# ws2812-cube-v1_2.net
KiCad netlist of a schematic drawn in EasyEDA
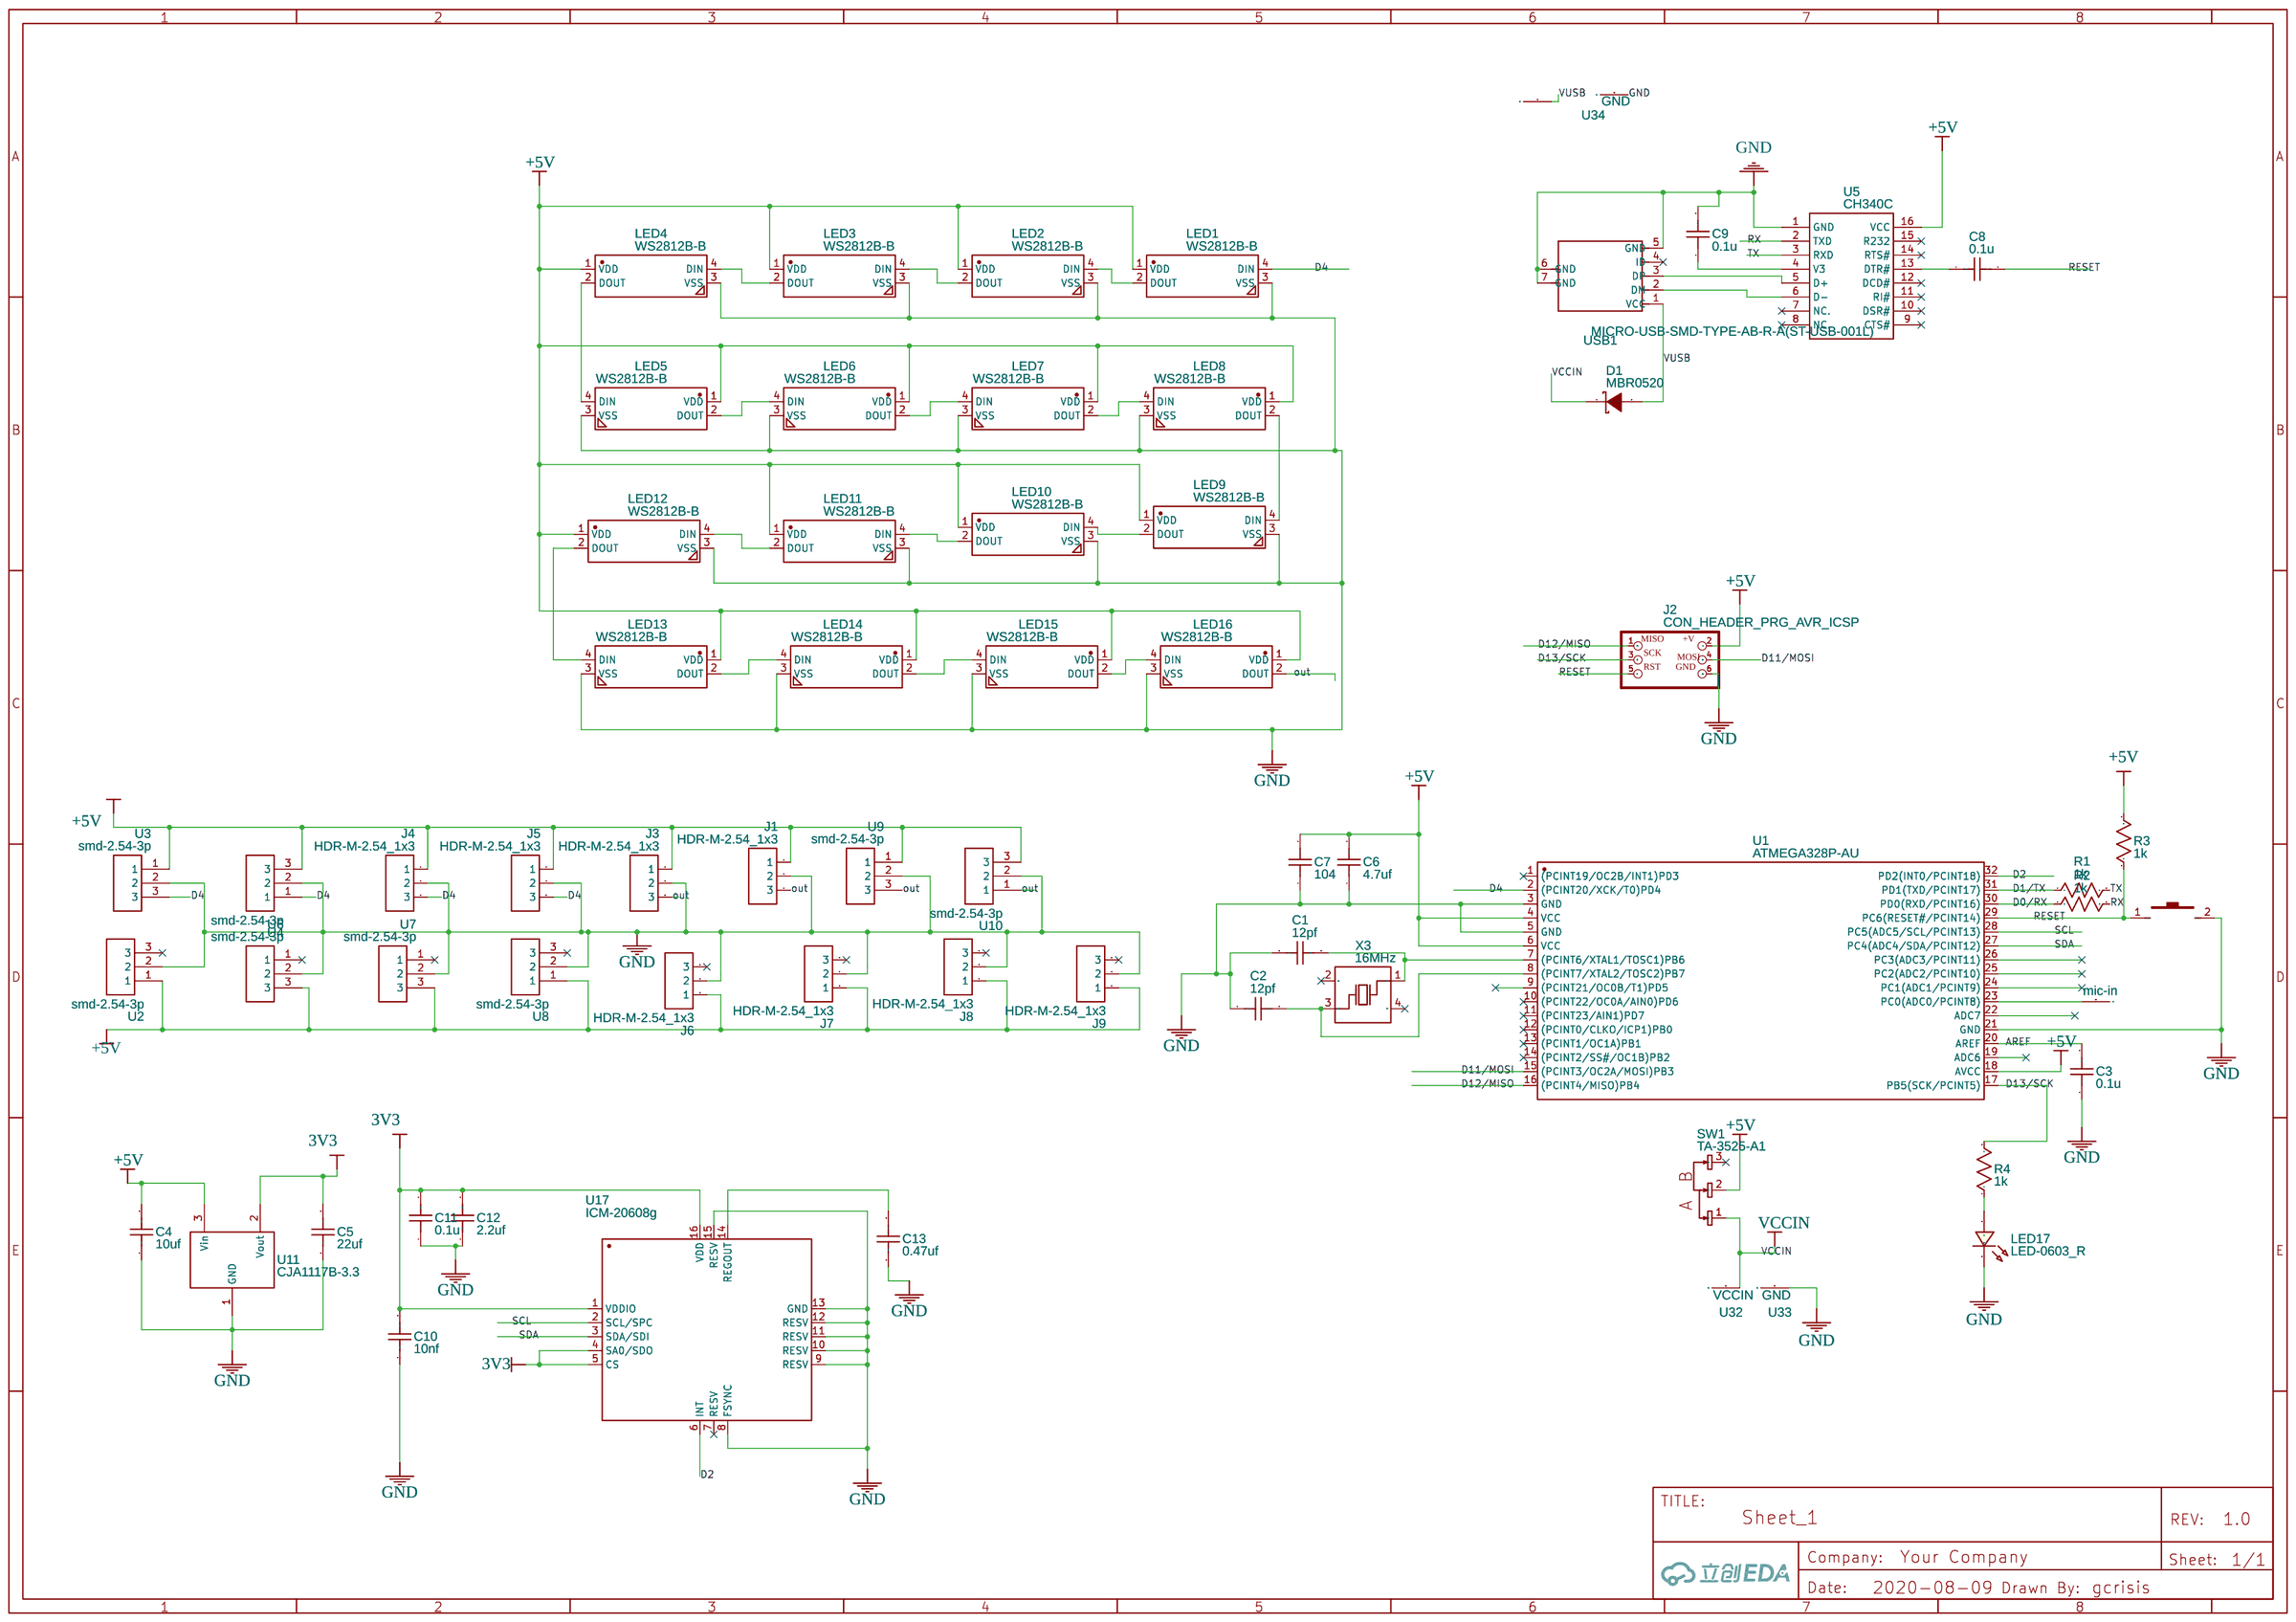
[diagram p0: schematic sheet]

(export (version "E")
  (design (tool "Eeschema 10.0.6"))
  (components
    (comp (ref "C1") (value "12pf") (libsource (lib "") (part "C_0603_US_1")))
    (comp (ref "C2") (value "12pf") (libsource (lib "") (part "C_0603_US_1")))
    (comp (ref "C3") (value "0.1u") (libsource (lib "") (part "C_0603_US")))
    (comp (ref "C4") (value "10uf") (libsource (lib "") (part "C_0603_US")))
    (comp (ref "C5") (value "22uf") (libsource (lib "") (part "C_0603_US")))
    (comp (ref "C6") (value "4.7uf") (libsource (lib "") (part "C_0603_US")))
    (comp (ref "C7") (value "104") (libsource (lib "") (part "C_0603_US")))
    (comp (ref "C8") (value "0.1u") (libsource (lib "") (part "C_0603_US_1")))
    (comp (ref "C9") (value "0.1u") (libsource (lib "") (part "C_0603_US")))
    (comp (ref "C10") (value "10nf") (libsource (lib "") (part "C_0603_US")))
    (comp (ref "C11") (value "0.1u") (libsource (lib "") (part "C_0603_US")))
    (comp (ref "C12") (value "2.2uf") (libsource (lib "") (part "C_0603_US")))
    (comp (ref "C13") (value "0.47uf") (libsource (lib "") (part "C_0603_US")))
    (comp (ref "D1")
      (value "MBR0520")
      (fields (field (name "BOM_Supplier Part") "C77335"))
      (libsource (lib "") (part "MBR0520"))
    )
    (comp (ref "J1")
      (value "HDR-M-2.54_1x3")
      (fields (field (name "BOM_Supplier Part") "C180248"))
      (libsource (lib "") (part "HDR-M-2.54_1x3_1"))
    )
    (comp (ref "J2") (value "CON_HEADER_PRG_AVR_ICSP") (libsource (lib "") (part "CON_HEADER_PRG_AVR_ICSP")))
    (comp (ref "J3")
      (value "HDR-M-2.54_1x3")
      (fields (field (name "BOM_Supplier Part") "C180248"))
      (libsource (lib "") (part "HDR-M-2.54_1x3_1"))
    )
    (comp (ref "J4")
      (value "HDR-M-2.54_1x3")
      (fields (field (name "BOM_Supplier Part") "C180248"))
      (libsource (lib "") (part "HDR-M-2.54_1x3_1"))
    )
    (comp (ref "J5")
      (value "HDR-M-2.54_1x3")
      (fields (field (name "BOM_Supplier Part") "C180248"))
      (libsource (lib "") (part "HDR-M-2.54_1x3_1"))
    )
    (comp (ref "J6")
      (value "HDR-M-2.54_1x3")
      (fields (field (name "BOM_Supplier Part") "C180248"))
      (libsource (lib "") (part "HDR-M-2.54_1x3"))
    )
    (comp (ref "J7")
      (value "HDR-M-2.54_1x3")
      (fields (field (name "BOM_Supplier Part") "C180248"))
      (libsource (lib "") (part "HDR-M-2.54_1x3"))
    )
    (comp (ref "J8")
      (value "HDR-M-2.54_1x3")
      (fields (field (name "BOM_Supplier Part") "C180248"))
      (libsource (lib "") (part "HDR-M-2.54_1x3"))
    )
    (comp (ref "J9")
      (value "HDR-M-2.54_1x3")
      (fields (field (name "BOM_Supplier Part") "C180248"))
      (libsource (lib "") (part "HDR-M-2.54_1x3"))
    )
    (comp (ref "KEY1")
      (value "3x6x2.5mm")
      (fields (field (name "BOM_Supplier Part") "C5382"))
      (libsource (lib "") (part "3x6x2.5mm"))
    )
    (comp (ref "LED1")
      (value "WS2812B-B")
      (fields (field (name "BOM_Supplier Part") "C114586"))
      (libsource (lib "") (part "WS2812B-B"))
    )
    (comp (ref "LED2")
      (value "WS2812B-B")
      (fields (field (name "BOM_Supplier Part") "C114586"))
      (libsource (lib "") (part "WS2812B-B"))
    )
    (comp (ref "LED3")
      (value "WS2812B-B")
      (fields (field (name "BOM_Supplier Part") "C114586"))
      (libsource (lib "") (part "WS2812B-B"))
    )
    (comp (ref "LED4")
      (value "WS2812B-B")
      (fields (field (name "BOM_Supplier Part") "C114586"))
      (libsource (lib "") (part "WS2812B-B"))
    )
    (comp (ref "LED5")
      (value "WS2812B-B")
      (fields (field (name "BOM_Supplier Part") "C114586"))
      (libsource (lib "") (part "WS2812B-B_1"))
    )
    (comp (ref "LED6")
      (value "WS2812B-B")
      (fields (field (name "BOM_Supplier Part") "C114586"))
      (libsource (lib "") (part "WS2812B-B_1"))
    )
    (comp (ref "LED7")
      (value "WS2812B-B")
      (fields (field (name "BOM_Supplier Part") "C114586"))
      (libsource (lib "") (part "WS2812B-B_1"))
    )
    (comp (ref "LED8")
      (value "WS2812B-B")
      (fields (field (name "BOM_Supplier Part") "C114586"))
      (libsource (lib "") (part "WS2812B-B_1"))
    )
    (comp (ref "LED9")
      (value "WS2812B-B")
      (fields (field (name "BOM_Supplier Part") "C114586"))
      (libsource (lib "") (part "WS2812B-B"))
    )
    (comp (ref "LED10")
      (value "WS2812B-B")
      (fields (field (name "BOM_Supplier Part") "C114586"))
      (libsource (lib "") (part "WS2812B-B"))
    )
    (comp (ref "LED11")
      (value "WS2812B-B")
      (fields (field (name "BOM_Supplier Part") "C114586"))
      (libsource (lib "") (part "WS2812B-B"))
    )
    (comp (ref "LED12")
      (value "WS2812B-B")
      (fields (field (name "BOM_Supplier Part") "C114586"))
      (libsource (lib "") (part "WS2812B-B"))
    )
    (comp (ref "LED13")
      (value "WS2812B-B")
      (fields (field (name "BOM_Supplier Part") "C114586"))
      (libsource (lib "") (part "WS2812B-B_1"))
    )
    (comp (ref "LED14")
      (value "WS2812B-B")
      (fields (field (name "BOM_Supplier Part") "C114586"))
      (libsource (lib "") (part "WS2812B-B_1"))
    )
    (comp (ref "LED15")
      (value "WS2812B-B")
      (fields (field (name "BOM_Supplier Part") "C114586"))
      (libsource (lib "") (part "WS2812B-B_1"))
    )
    (comp (ref "LED16")
      (value "WS2812B-B")
      (fields (field (name "BOM_Supplier Part") "C114586"))
      (libsource (lib "") (part "WS2812B-B_1"))
    )
    (comp (ref "LED17")
      (value "LED-0603_R")
      (fields
        (field (name "BOM_Manufacturer Part") "19-217/R6C-AL1M2VY/3T")
        (field (name "BOM_Supplier Part") "C72044")
      )
      (libsource (lib "") (part "LED-0603_R"))
    )
    (comp (ref "R1") (value "1k") (libsource (lib "") (part "R_0603_US_1")))
    (comp (ref "R2") (value "1k") (libsource (lib "") (part "R_0603_US_1")))
    (comp (ref "R3") (value "1k") (libsource (lib "") (part "R_0603_US")))
    (comp (ref "R4") (value "1k") (libsource (lib "") (part "R_0603_US")))
    (comp (ref "SW1")
      (value "TA-3525-A1")
      (fields (field (name "BOM_Supplier Part") "C514018"))
      (libsource (lib "") (part "TA-3525-A1"))
    )
    (comp (ref "U1")
      (value "ATMEGA328P-AU")
      (fields (field (name "BOM_Supplier Part") "C14877"))
      (libsource (lib "") (part "ATMEGA328P-AU"))
    )
    (comp (ref "U2") (value "smd-2.54-3p") (libsource (lib "") (part "smd-2.54-3p")))
    (comp (ref "U3") (value "smd-2.54-3p") (libsource (lib "") (part "smd-2.54-3p_1")))
    (comp (ref "U4") (value "smd-2.54-3p") (libsource (lib "") (part "smd-2.54-3p")))
    (comp (ref "U5")
      (value "CH340C")
      (fields (field (name "BOM_Supplier Part") "C84681"))
      (libsource (lib "") (part "CH340C"))
    )
    (comp (ref "U6") (value "smd-2.54-3p") (libsource (lib "") (part "smd-2.54-3p_1")))
    (comp (ref "U7") (value "smd-2.54-3p") (libsource (lib "") (part "smd-2.54-3p_1")))
    (comp (ref "U8") (value "smd-2.54-3p") (libsource (lib "") (part "smd-2.54-3p")))
    (comp (ref "U9") (value "smd-2.54-3p") (libsource (lib "") (part "smd-2.54-3p_1")))
    (comp (ref "U10") (value "smd-2.54-3p") (libsource (lib "") (part "smd-2.54-3p")))
    (comp (ref "U11")
      (value "CJA1117B-3.3")
      (fields (field (name "BOM_Supplier Part") "C24253"))
      (libsource (lib "") (part "CJA1117B-3.3"))
    )
    (comp (ref "U12") (value "mic-in") (libsource (lib "") (part "PAD_1")))
    (comp (ref "U17")
      (value "ICM-20608g")
      (fields (field (name "BOM_Manufacturer Part") "ICM-20602") (field (name "BOM_Supplier Part") "C97633"))
      (libsource (lib "") (part "ICM-20602"))
    )
    (comp (ref "U32") (value "VCCIN") (libsource (lib "") (part "PAD")))
    (comp (ref "U33") (value "GND") (libsource (lib "") (part "PAD")))
    (comp (ref "U34") (value "GND") (libsource (lib "") (part "PAD")))
    (comp (ref "U35") (value "VUSB") (libsource (lib "") (part "PAD")))
    (comp (ref "USB1")
      (value "MICRO-USB-SMD-TYPE-AB-R-A(ST-USB-001L)")
      (fields (field (name "BOM_Manufacturer Part") "?"))
      (libsource (lib "") (part "MICRO-USB-SMD-TYPE-AB-R-A(ST-USB-001L)"))
    )
    (comp (ref "X3")
      (value "16MHz")
      (fields
        (field (name "BOM_Manufacturer Part") "X1E0000210375000G")
        (field (name "BOM_Supplier Part") "C89379")
      )
      (libsource (lib "") (part "X1E0000210375000G"))
    )
  )
  (nets
    (net (code "1") (name "+5V") (class "Default")
      (node (ref "C4") (pin "2") (pinfunction "2_2") (pintype "unspecified"))
      (node (ref "C6") (pin "2") (pinfunction "2_2") (pintype "unspecified"))
      (node (ref "C7") (pin "2") (pinfunction "2_2") (pintype "unspecified"))
      (node (ref "J1") (pin "1") (pinfunction "1_1") (pintype "input"))
      (node (ref "J2") (pin "2") (pinfunction "+V_2") (pintype "unspecified"))
      (node (ref "J3") (pin "1") (pinfunction "1_1") (pintype "input"))
      (node (ref "J4") (pin "1") (pinfunction "1_1") (pintype "input"))
      (node (ref "J5") (pin "1") (pinfunction "1_1") (pintype "input"))
      (node (ref "J6") (pin "1") (pinfunction "1_1") (pintype "input"))
      (node (ref "J7") (pin "1") (pinfunction "1_1") (pintype "input"))
      (node (ref "J8") (pin "1") (pinfunction "1_1") (pintype "input"))
      (node (ref "J9") (pin "1") (pinfunction "1_1") (pintype "input"))
      (node (ref "LED1") (pin "1") (pinfunction "VDD_1") (pintype "unspecified"))
      (node (ref "LED10") (pin "1") (pinfunction "VDD_1") (pintype "unspecified"))
      (node (ref "LED11") (pin "1") (pinfunction "VDD_1") (pintype "unspecified"))
      (node (ref "LED12") (pin "1") (pinfunction "VDD_1") (pintype "unspecified"))
      (node (ref "LED13") (pin "1") (pinfunction "VDD_1") (pintype "unspecified"))
      (node (ref "LED14") (pin "1") (pinfunction "VDD_1") (pintype "unspecified"))
      (node (ref "LED15") (pin "1") (pinfunction "VDD_1") (pintype "unspecified"))
      (node (ref "LED16") (pin "1") (pinfunction "VDD_1") (pintype "unspecified"))
      (node (ref "LED2") (pin "1") (pinfunction "VDD_1") (pintype "unspecified"))
      (node (ref "LED3") (pin "1") (pinfunction "VDD_1") (pintype "unspecified"))
      (node (ref "LED4") (pin "1") (pinfunction "VDD_1") (pintype "unspecified"))
      (node (ref "LED5") (pin "1") (pinfunction "VDD_1") (pintype "unspecified"))
      (node (ref "LED6") (pin "1") (pinfunction "VDD_1") (pintype "unspecified"))
      (node (ref "LED7") (pin "1") (pinfunction "VDD_1") (pintype "unspecified"))
      (node (ref "LED8") (pin "1") (pinfunction "VDD_1") (pintype "unspecified"))
      (node (ref "LED9") (pin "1") (pinfunction "VDD_1") (pintype "unspecified"))
      (node (ref "R3") (pin "2") (pinfunction "2_2") (pintype "unspecified"))
      (node (ref "SW1") (pin "2") (pinfunction "2_2") (pintype "unspecified"))
      (node (ref "U1") (pin "18") (pinfunction "AVCC_18") (pintype "unspecified"))
      (node (ref "U1") (pin "4") (pinfunction "VCC_4") (pintype "unspecified"))
      (node (ref "U1") (pin "6") (pinfunction "VCC_6") (pintype "unspecified"))
      (node (ref "U10") (pin "3") (pinfunction "3_3") (pintype "unspecified"))
      (node (ref "U11") (pin "3") (pinfunction "Vin_3") (pintype "unspecified"))
      (node (ref "U2") (pin "1") (pinfunction "1_1") (pintype "unspecified"))
      (node (ref "U3") (pin "1") (pinfunction "1_1") (pintype "unspecified"))
      (node (ref "U4") (pin "3") (pinfunction "3_3") (pintype "unspecified"))
      (node (ref "U5") (pin "16") (pinfunction "VCC_16") (pintype "unspecified"))
      (node (ref "U6") (pin "3") (pinfunction "3_3") (pintype "unspecified"))
      (node (ref "U7") (pin "3") (pinfunction "3_3") (pintype "unspecified"))
      (node (ref "U8") (pin "1") (pinfunction "1_1") (pintype "unspecified"))
      (node (ref "U9") (pin "1") (pinfunction "1_1") (pintype "unspecified"))
    )
    (net (code "2") (name "/AREF") (class "Default")
      (node (ref "C3") (pin "2") (pinfunction "2_2") (pintype "unspecified"))
      (node (ref "U1") (pin "20") (pinfunction "AREF_20") (pintype "unspecified"))
    )
    (net (code "3") (name "/D0{slash}RX") (class "Default")
      (node (ref "R2") (pin "1") (pinfunction "1_1") (pintype "unspecified"))
      (node (ref "U1") (pin "30") (pinfunction "PD0(RXD/PCINT16)_30") (pintype "unspecified"))
    )
    (net (code "4") (name "/D1{slash}TX") (class "Default")
      (node (ref "R1") (pin "1") (pinfunction "1_1") (pintype "unspecified"))
      (node (ref "U1") (pin "31") (pinfunction "PD1(TXD/PCINT17)_31") (pintype "unspecified"))
    )
    (net (code "5") (name "/D2") (class "Default")
      (node (ref "U1") (pin "32") (pinfunction "PD2(INT0/PCINT18)_32") (pintype "unspecified"))
      (node (ref "U17") (pin "6") (pinfunction "INT_6") (pintype "unspecified"))
    )
    (net (code "6") (name "/D4") (class "Default")
      (node (ref "J4") (pin "3") (pinfunction "3_3") (pintype "input"))
      (node (ref "J5") (pin "3") (pinfunction "3_3") (pintype "input"))
      (node (ref "LED1") (pin "4") (pinfunction "DIN_4") (pintype "unspecified"))
      (node (ref "U1") (pin "2") (pinfunction "(PCINT20/XCK/T0)PD4_2") (pintype "unspecified"))
      (node (ref "U3") (pin "3") (pinfunction "3_3") (pintype "unspecified"))
      (node (ref "U4") (pin "1") (pinfunction "1_1") (pintype "unspecified"))
    )
    (net (code "7") (name "/D11{slash}MOSI") (class "Default")
      (node (ref "J2") (pin "4") (pinfunction "MOSI_4") (pintype "unspecified"))
      (node (ref "U1") (pin "15") (pinfunction "(PCINT3/OC2A/MOSI)PB3_15") (pintype "unspecified"))
    )
    (net (code "8") (name "/D12{slash}MISO") (class "Default")
      (node (ref "J2") (pin "1") (pinfunction "MISO_1") (pintype "unspecified"))
      (node (ref "U1") (pin "16") (pinfunction "(PCINT4/MISO)PB4_16") (pintype "unspecified"))
    )
    (net (code "9") (name "/D13{slash}SCK") (class "Default")
      (node (ref "J2") (pin "3") (pinfunction "SCK_3") (pintype "unspecified"))
      (node (ref "R4") (pin "2") (pinfunction "2_2") (pintype "unspecified"))
      (node (ref "U1") (pin "17") (pinfunction "PB5(SCK/PCINT5)_17") (pintype "unspecified"))
    )
    (net (code "10") (name "/RESET") (class "Default")
      (node (ref "C8") (pin "2") (pinfunction "2_2") (pintype "unspecified"))
      (node (ref "J2") (pin "5") (pinfunction "RST_5") (pintype "unspecified"))
      (node (ref "KEY1") (pin "1") (pinfunction "1_1") (pintype "input"))
      (node (ref "R3") (pin "1") (pinfunction "1_1") (pintype "unspecified"))
      (node (ref "U1") (pin "29") (pinfunction "PC6(RESET#/PCINT14)_29") (pintype "unspecified"))
    )
    (net (code "11") (name "/RX") (class "Default")
      (node (ref "R2") (pin "2") (pinfunction "2_2") (pintype "unspecified"))
      (node (ref "U5") (pin "2") (pinfunction "TXD_2") (pintype "unspecified"))
    )
    (net (code "12") (name "/SCL") (class "Default")
      (node (ref "U1") (pin "28") (pinfunction "PC5(ADC5/SCL/PCINT13)_28") (pintype "unspecified"))
      (node (ref "U17") (pin "2") (pinfunction "SCL/SPC_2") (pintype "unspecified"))
    )
    (net (code "13") (name "/SDA") (class "Default")
      (node (ref "U1") (pin "27") (pinfunction "PC4(ADC4/SDA/PCINT12)_27") (pintype "unspecified"))
      (node (ref "U17") (pin "3") (pinfunction "SDA/SDI_3") (pintype "unspecified"))
    )
    (net (code "14") (name "/TX") (class "Default")
      (node (ref "R1") (pin "2") (pinfunction "2_2") (pintype "unspecified"))
      (node (ref "U5") (pin "3") (pinfunction "RXD_3") (pintype "unspecified"))
    )
    (net (code "15") (name "/VUSB") (class "Default")
      (node (ref "D1") (pin "2") (pinfunction "A_2") (pintype "unspecified"))
      (node (ref "U35") (pin "P$1") (pinfunction "P$1_P$1") (pintype "unspecified"))
      (node (ref "USB1") (pin "1") (pinfunction "VCC_1") (pintype "unspecified"))
    )
    (net (code "16") (name "/out") (class "Default")
      (node (ref "J1") (pin "3") (pinfunction "3_3") (pintype "input"))
      (node (ref "J3") (pin "3") (pinfunction "3_3") (pintype "input"))
      (node (ref "LED16") (pin "2") (pinfunction "DOUT_2") (pintype "unspecified"))
      (node (ref "U10") (pin "1") (pinfunction "1_1") (pintype "unspecified"))
      (node (ref "U9") (pin "3") (pinfunction "3_3") (pintype "unspecified"))
    )
    (net (code "17") (name "3V3") (class "Default")
      (node (ref "C10") (pin "2") (pinfunction "2_2") (pintype "unspecified"))
      (node (ref "C11") (pin "2") (pinfunction "2_2") (pintype "unspecified"))
      (node (ref "C12") (pin "2") (pinfunction "2_2") (pintype "unspecified"))
      (node (ref "C5") (pin "2") (pinfunction "2_2") (pintype "unspecified"))
      (node (ref "U11") (pin "2") (pinfunction "Vout_2") (pintype "unspecified"))
      (node (ref "U17") (pin "1") (pinfunction "VDDIO_1") (pintype "unspecified"))
      (node (ref "U17") (pin "16") (pinfunction "VDD_16") (pintype "unspecified"))
      (node (ref "U17") (pin "4") (pinfunction "SA0/SDO_4") (pintype "unspecified"))
      (node (ref "U17") (pin "5") (pinfunction "CS_5") (pintype "unspecified"))
    )
    (net (code "18") (name "GND") (class "Default")
      (node (ref "C1") (pin "1") (pinfunction "1_1") (pintype "unspecified"))
      (node (ref "C10") (pin "1") (pinfunction "1_1") (pintype "unspecified"))
      (node (ref "C11") (pin "1") (pinfunction "1_1") (pintype "unspecified"))
      (node (ref "C12") (pin "1") (pinfunction "1_1") (pintype "unspecified"))
      (node (ref "C13") (pin "1") (pinfunction "1_1") (pintype "unspecified"))
      (node (ref "C2") (pin "1") (pinfunction "1_1") (pintype "unspecified"))
      (node (ref "C3") (pin "1") (pinfunction "1_1") (pintype "unspecified"))
      (node (ref "C4") (pin "1") (pinfunction "1_1") (pintype "unspecified"))
      (node (ref "C5") (pin "1") (pinfunction "1_1") (pintype "unspecified"))
      (node (ref "C6") (pin "1") (pinfunction "1_1") (pintype "unspecified"))
      (node (ref "C7") (pin "1") (pinfunction "1_1") (pintype "unspecified"))
      (node (ref "C9") (pin "2") (pinfunction "2_2") (pintype "unspecified"))
      (node (ref "J1") (pin "2") (pinfunction "2_2") (pintype "input"))
      (node (ref "J2") (pin "6") (pinfunction "GND_6") (pintype "unspecified"))
      (node (ref "J3") (pin "2") (pinfunction "2_2") (pintype "input"))
      (node (ref "J4") (pin "2") (pinfunction "2_2") (pintype "input"))
      (node (ref "J5") (pin "2") (pinfunction "2_2") (pintype "input"))
      (node (ref "J6") (pin "2") (pinfunction "2_2") (pintype "input"))
      (node (ref "J7") (pin "2") (pinfunction "2_2") (pintype "input"))
      (node (ref "J8") (pin "2") (pinfunction "2_2") (pintype "input"))
      (node (ref "J9") (pin "2") (pinfunction "2_2") (pintype "input"))
      (node (ref "KEY1") (pin "2") (pinfunction "2_2") (pintype "input"))
      (node (ref "LED1") (pin "3") (pinfunction "VSS_3") (pintype "unspecified"))
      (node (ref "LED10") (pin "3") (pinfunction "VSS_3") (pintype "unspecified"))
      (node (ref "LED11") (pin "3") (pinfunction "VSS_3") (pintype "unspecified"))
      (node (ref "LED12") (pin "3") (pinfunction "VSS_3") (pintype "unspecified"))
      (node (ref "LED13") (pin "3") (pinfunction "VSS_3") (pintype "unspecified"))
      (node (ref "LED14") (pin "3") (pinfunction "VSS_3") (pintype "unspecified"))
      (node (ref "LED15") (pin "3") (pinfunction "VSS_3") (pintype "unspecified"))
      (node (ref "LED16") (pin "3") (pinfunction "VSS_3") (pintype "unspecified"))
      (node (ref "LED17") (pin "2") (pinfunction "2_2") (pintype "unspecified"))
      (node (ref "LED2") (pin "3") (pinfunction "VSS_3") (pintype "unspecified"))
      (node (ref "LED3") (pin "3") (pinfunction "VSS_3") (pintype "unspecified"))
      (node (ref "LED4") (pin "3") (pinfunction "VSS_3") (pintype "unspecified"))
      (node (ref "LED5") (pin "3") (pinfunction "VSS_3") (pintype "unspecified"))
      (node (ref "LED6") (pin "3") (pinfunction "VSS_3") (pintype "unspecified"))
      (node (ref "LED7") (pin "3") (pinfunction "VSS_3") (pintype "unspecified"))
      (node (ref "LED8") (pin "3") (pinfunction "VSS_3") (pintype "unspecified"))
      (node (ref "LED9") (pin "3") (pinfunction "VSS_3") (pintype "unspecified"))
      (node (ref "U1") (pin "21") (pinfunction "GND_21") (pintype "unspecified"))
      (node (ref "U1") (pin "3") (pinfunction "GND_3") (pintype "unspecified"))
      (node (ref "U1") (pin "5") (pinfunction "GND_5") (pintype "unspecified"))
      (node (ref "U10") (pin "2") (pinfunction "2_2") (pintype "unspecified"))
      (node (ref "U11") (pin "1") (pinfunction "GND_1") (pintype "unspecified"))
      (node (ref "U17") (pin "10") (pinfunction "RESV_10") (pintype "unspecified"))
      (node (ref "U17") (pin "11") (pinfunction "RESV_11") (pintype "unspecified"))
      (node (ref "U17") (pin "12") (pinfunction "RESV_12") (pintype "unspecified"))
      (node (ref "U17") (pin "13") (pinfunction "GND_13") (pintype "unspecified"))
      (node (ref "U17") (pin "15") (pinfunction "RESV_15") (pintype "unspecified"))
      (node (ref "U17") (pin "8") (pinfunction "FSYNC_8") (pintype "unspecified"))
      (node (ref "U17") (pin "9") (pinfunction "RESV_9") (pintype "unspecified"))
      (node (ref "U2") (pin "2") (pinfunction "2_2") (pintype "unspecified"))
      (node (ref "U3") (pin "2") (pinfunction "2_2") (pintype "unspecified"))
      (node (ref "U33") (pin "P$1") (pinfunction "P$1_P$1") (pintype "unspecified"))
      (node (ref "U34") (pin "P$1") (pinfunction "P$1_P$1") (pintype "unspecified"))
      (node (ref "U4") (pin "2") (pinfunction "2_2") (pintype "unspecified"))
      (node (ref "U5") (pin "1") (pinfunction "GND_1") (pintype "unspecified"))
      (node (ref "U6") (pin "2") (pinfunction "2_2") (pintype "unspecified"))
      (node (ref "U7") (pin "2") (pinfunction "2_2") (pintype "unspecified"))
      (node (ref "U8") (pin "2") (pinfunction "2_2") (pintype "unspecified"))
      (node (ref "U9") (pin "2") (pinfunction "2_2") (pintype "unspecified"))
      (node (ref "USB1") (pin "5") (pinfunction "GND_5") (pintype "unspecified"))
      (node (ref "USB1") (pin "6") (pinfunction "GND_6") (pintype "unspecified"))
      (node (ref "USB1") (pin "7") (pinfunction "GND_7") (pintype "unspecified"))
    )
    (net (code "19") (name "Net-(LED1-DOUT)") (class "Default")
      (node (ref "LED1") (pin "2") (pinfunction "DOUT_2") (pintype "unspecified"))
      (node (ref "LED2") (pin "4") (pinfunction "DIN_4") (pintype "unspecified"))
    )
    (net (code "20") (name "Net-(LED2-DOUT)") (class "Default")
      (node (ref "LED2") (pin "2") (pinfunction "DOUT_2") (pintype "unspecified"))
      (node (ref "LED3") (pin "4") (pinfunction "DIN_4") (pintype "unspecified"))
    )
    (net (code "21") (name "Net-(LED3-DOUT)") (class "Default")
      (node (ref "LED3") (pin "2") (pinfunction "DOUT_2") (pintype "unspecified"))
      (node (ref "LED4") (pin "4") (pinfunction "DIN_4") (pintype "unspecified"))
    )
    (net (code "22") (name "Net-(LED4-DOUT)") (class "Default")
      (node (ref "LED4") (pin "2") (pinfunction "DOUT_2") (pintype "unspecified"))
      (node (ref "LED5") (pin "4") (pinfunction "DIN_4") (pintype "unspecified"))
    )
    (net (code "23") (name "Net-(LED5-DOUT)") (class "Default")
      (node (ref "LED5") (pin "2") (pinfunction "DOUT_2") (pintype "unspecified"))
      (node (ref "LED6") (pin "4") (pinfunction "DIN_4") (pintype "unspecified"))
    )
    (net (code "24") (name "Net-(LED6-DOUT)") (class "Default")
      (node (ref "LED6") (pin "2") (pinfunction "DOUT_2") (pintype "unspecified"))
      (node (ref "LED7") (pin "4") (pinfunction "DIN_4") (pintype "unspecified"))
    )
    (net (code "25") (name "Net-(LED7-DOUT)") (class "Default")
      (node (ref "LED7") (pin "2") (pinfunction "DOUT_2") (pintype "unspecified"))
      (node (ref "LED8") (pin "4") (pinfunction "DIN_4") (pintype "unspecified"))
    )
    (net (code "26") (name "Net-(LED8-DOUT)") (class "Default")
      (node (ref "LED8") (pin "2") (pinfunction "DOUT_2") (pintype "unspecified"))
      (node (ref "LED9") (pin "4") (pinfunction "DIN_4") (pintype "unspecified"))
    )
    (net (code "27") (name "Net-(LED10-DIN)") (class "Default")
      (node (ref "LED10") (pin "4") (pinfunction "DIN_4") (pintype "unspecified"))
      (node (ref "LED9") (pin "2") (pinfunction "DOUT_2") (pintype "unspecified"))
    )
    (net (code "28") (name "Net-(LED10-DOUT)") (class "Default")
      (node (ref "LED10") (pin "2") (pinfunction "DOUT_2") (pintype "unspecified"))
      (node (ref "LED11") (pin "4") (pinfunction "DIN_4") (pintype "unspecified"))
    )
    (net (code "29") (name "Net-(LED11-DOUT)") (class "Default")
      (node (ref "LED11") (pin "2") (pinfunction "DOUT_2") (pintype "unspecified"))
      (node (ref "LED12") (pin "4") (pinfunction "DIN_4") (pintype "unspecified"))
    )
    (net (code "30") (name "Net-(LED12-DOUT)") (class "Default")
      (node (ref "LED12") (pin "2") (pinfunction "DOUT_2") (pintype "unspecified"))
      (node (ref "LED13") (pin "4") (pinfunction "DIN_4") (pintype "unspecified"))
    )
    (net (code "31") (name "Net-(LED13-DOUT)") (class "Default")
      (node (ref "LED13") (pin "2") (pinfunction "DOUT_2") (pintype "unspecified"))
      (node (ref "LED14") (pin "4") (pinfunction "DIN_4") (pintype "unspecified"))
    )
    (net (code "32") (name "Net-(LED14-DOUT)") (class "Default")
      (node (ref "LED14") (pin "2") (pinfunction "DOUT_2") (pintype "unspecified"))
      (node (ref "LED15") (pin "4") (pinfunction "DIN_4") (pintype "unspecified"))
    )
    (net (code "33") (name "Net-(LED15-DOUT)") (class "Default")
      (node (ref "LED15") (pin "2") (pinfunction "DOUT_2") (pintype "unspecified"))
      (node (ref "LED16") (pin "4") (pinfunction "DIN_4") (pintype "unspecified"))
    )
    (net (code "34") (name "Net-(LED17-Pad1)") (class "Default")
      (node (ref "LED17") (pin "1") (pinfunction "1_1") (pintype "unspecified"))
      (node (ref "R4") (pin "1") (pinfunction "1_1") (pintype "unspecified"))
    )
    (net (code "35") (name "Net-(U1-(PCINT6{slash}XTAL1{slash}TOSC1)PB6)") (class "Default")
      (node (ref "C1") (pin "2") (pinfunction "2_2") (pintype "unspecified"))
      (node (ref "U1") (pin "7") (pinfunction "(PCINT6/XTAL1/TOSC1)PB6_7") (pintype "unspecified"))
      (node (ref "X3") (pin "1") (pinfunction "OSC1_1") (pintype "unspecified"))
    )
    (net (code "36") (name "Net-(U1-(PCINT7{slash}XTAL2{slash}TOSC2)PB7)") (class "Default")
      (node (ref "C2") (pin "2") (pinfunction "2_2") (pintype "unspecified"))
      (node (ref "U1") (pin "8") (pinfunction "(PCINT7/XTAL2/TOSC2)PB7_8") (pintype "unspecified"))
      (node (ref "X3") (pin "3") (pinfunction "OSC2_3") (pintype "unspecified"))
    )
    (net (code "37") (name "Net-(U1-PC0(ADC0{slash}PCINT8))") (class "Default")
      (node (ref "U1") (pin "23") (pinfunction "PC0(ADC0/PCINT8)_23") (pintype "unspecified"))
      (node (ref "U12") (pin "P$1") (pinfunction "P$1_P$1") (pintype "unspecified"))
    )
    (net (code "38") (name "Net-(U5-D+)") (class "Default")
      (node (ref "U5") (pin "5") (pinfunction "D+_5") (pintype "unspecified"))
      (node (ref "USB1") (pin "3") (pinfunction "DP_3") (pintype "unspecified"))
    )
    (net (code "39") (name "Net-(U5-D-)") (class "Default")
      (node (ref "U5") (pin "6") (pinfunction "D-_6") (pintype "unspecified"))
      (node (ref "USB1") (pin "2") (pinfunction "DM_2") (pintype "unspecified"))
    )
    (net (code "40") (name "Net-(U5-DTR#)") (class "Default")
      (node (ref "C8") (pin "1") (pinfunction "1_1") (pintype "unspecified"))
      (node (ref "U5") (pin "13") (pinfunction "DTR#_13") (pintype "unspecified"))
    )
    (net (code "41") (name "Net-(U5-V3)") (class "Default")
      (node (ref "C9") (pin "1") (pinfunction "1_1") (pintype "unspecified"))
      (node (ref "U5") (pin "4") (pinfunction "V3_4") (pintype "unspecified"))
    )
    (net (code "42") (name "Net-(U17-REGOUT)") (class "Default")
      (node (ref "C13") (pin "2") (pinfunction "2_2") (pintype "unspecified"))
      (node (ref "U17") (pin "14") (pinfunction "REGOUT_14") (pintype "unspecified"))
    )
    (net (code "43") (name "VCCIN") (class "Default")
      (node (ref "D1") (pin "1") (pinfunction "K_1") (pintype "unspecified"))
      (node (ref "SW1") (pin "1") (pinfunction "1_1") (pintype "unspecified"))
      (node (ref "U32") (pin "P$1") (pinfunction "P$1_P$1") (pintype "unspecified"))
    )
    (net (code "44") (name "unconnected-(J6-Pad3)") (class "Default")
      (node (ref "J6") (pin "3") (pinfunction "3_3") (pintype "input+no_connect"))
    )
    (net (code "45") (name "unconnected-(J7-Pad3)") (class "Default")
      (node (ref "J7") (pin "3") (pinfunction "3_3") (pintype "input+no_connect"))
    )
    (net (code "46") (name "unconnected-(J8-Pad3)") (class "Default")
      (node (ref "J8") (pin "3") (pinfunction "3_3") (pintype "input+no_connect"))
    )
    (net (code "47") (name "unconnected-(J9-Pad3)") (class "Default")
      (node (ref "J9") (pin "3") (pinfunction "3_3") (pintype "input+no_connect"))
    )
    (net (code "48") (name "unconnected-(SW1-Pad3)") (class "Default")
      (node (ref "SW1") (pin "3") (pinfunction "3_3") (pintype "unspecified+no_connect"))
    )
    (net (code "49") (name "unconnected-(U1-(PCINT0{slash}CLKO{slash}ICP1)PB0-Pad12)") (class "Default")
      (node (ref "U1") (pin "12") (pinfunction "(PCINT0/CLKO/ICP1)PB0_12") (pintype "unspecified+no_connect"))
    )
    (net (code "50") (name "unconnected-(U1-(PCINT1{slash}OC1A)PB1-Pad13)") (class "Default")
      (node (ref "U1") (pin "13") (pinfunction "(PCINT1/OC1A)PB1_13") (pintype "unspecified+no_connect"))
    )
    (net (code "51") (name "unconnected-(U1-(PCINT2{slash}SS#{slash}OC1B)PB2-Pad14)") (class "Default")
      (node (ref "U1") (pin "14") (pinfunction "(PCINT2/SS#/OC1B)PB2_14") (pintype "unspecified+no_connect"))
    )
    (net (code "52") (name "unconnected-(U1-(PCINT19{slash}OC2B{slash}INT1)PD3-Pad1)") (class "Default")
      (node (ref "U1") (pin "1") (pinfunction "(PCINT19/OC2B/INT1)PD3_1") (pintype "unspecified+no_connect"))
    )
    (net (code "53") (name "unconnected-(U1-(PCINT21{slash}OC0B{slash}T1)PD5-Pad9)") (class "Default")
      (node (ref "U1") (pin "9") (pinfunction "(PCINT21/OC0B/T1)PD5_9") (pintype "unspecified+no_connect"))
    )
    (net (code "54") (name "unconnected-(U1-(PCINT22{slash}OC0A{slash}AIN0)PD6-Pad10)") (class "Default")
      (node (ref "U1") (pin "10") (pinfunction "(PCINT22/OC0A/AIN0)PD6_10") (pintype "unspecified+no_connect"))
    )
    (net (code "55") (name "unconnected-(U1-(PCINT23{slash}AIN1)PD7-Pad11)") (class "Default")
      (node (ref "U1") (pin "11") (pinfunction "(PCINT23/AIN1)PD7_11") (pintype "unspecified+no_connect"))
    )
    (net (code "56") (name "unconnected-(U1-ADC6-Pad19)") (class "Default")
      (node (ref "U1") (pin "19") (pinfunction "ADC6_19") (pintype "unspecified+no_connect"))
    )
    (net (code "57") (name "unconnected-(U1-ADC7-Pad22)") (class "Default")
      (node (ref "U1") (pin "22") (pinfunction "ADC7_22") (pintype "unspecified+no_connect"))
    )
    (net (code "58") (name "unconnected-(U1-PC1(ADC1{slash}PCINT9)-Pad24)") (class "Default")
      (node (ref "U1") (pin "24") (pinfunction "PC1(ADC1/PCINT9)_24") (pintype "unspecified+no_connect"))
    )
    (net (code "59") (name "unconnected-(U1-PC2(ADC2{slash}PCINT10)-Pad25)") (class "Default")
      (node (ref "U1") (pin "25") (pinfunction "PC2(ADC2/PCINT10)_25") (pintype "unspecified+no_connect"))
    )
    (net (code "60") (name "unconnected-(U1-PC3(ADC3{slash}PCINT11)-Pad26)") (class "Default")
      (node (ref "U1") (pin "26") (pinfunction "PC3(ADC3/PCINT11)_26") (pintype "unspecified+no_connect"))
    )
    (net (code "61") (name "unconnected-(U2-Pad3)") (class "Default")
      (node (ref "U2") (pin "3") (pinfunction "3_3") (pintype "unspecified+no_connect"))
    )
    (net (code "62") (name "unconnected-(U5-CTS#-Pad9)") (class "Default")
      (node (ref "U5") (pin "9") (pinfunction "CTS#_9") (pintype "unspecified+no_connect"))
    )
    (net (code "63") (name "unconnected-(U5-DCD#-Pad12)") (class "Default")
      (node (ref "U5") (pin "12") (pinfunction "DCD#_12") (pintype "unspecified+no_connect"))
    )
    (net (code "64") (name "unconnected-(U5-DSR#-Pad10)") (class "Default")
      (node (ref "U5") (pin "10") (pinfunction "DSR#_10") (pintype "unspecified+no_connect"))
    )
    (net (code "65") (name "unconnected-(U5-NC.-Pad7)") (class "Default")
      (node (ref "U5") (pin "7") (pinfunction "NC._7") (pintype "unspecified+no_connect"))
    )
    (net (code "66") (name "unconnected-(U5-NC.-Pad8)") (class "Default")
      (node (ref "U5") (pin "8") (pinfunction "NC._8") (pintype "unspecified+no_connect"))
    )
    (net (code "67") (name "unconnected-(U5-R232-Pad15)") (class "Default")
      (node (ref "U5") (pin "15") (pinfunction "R232_15") (pintype "unspecified+no_connect"))
    )
    (net (code "68") (name "unconnected-(U5-RI#-Pad11)") (class "Default")
      (node (ref "U5") (pin "11") (pinfunction "RI#_11") (pintype "unspecified+no_connect"))
    )
    (net (code "69") (name "unconnected-(U5-RTS#-Pad14)") (class "Default")
      (node (ref "U5") (pin "14") (pinfunction "RTS#_14") (pintype "unspecified+no_connect"))
    )
    (net (code "70") (name "unconnected-(U6-Pad1)") (class "Default")
      (node (ref "U6") (pin "1") (pinfunction "1_1") (pintype "unspecified+no_connect"))
    )
    (net (code "71") (name "unconnected-(U7-Pad1)") (class "Default")
      (node (ref "U7") (pin "1") (pinfunction "1_1") (pintype "unspecified+no_connect"))
    )
    (net (code "72") (name "unconnected-(U8-Pad3)") (class "Default")
      (node (ref "U8") (pin "3") (pinfunction "3_3") (pintype "unspecified+no_connect"))
    )
    (net (code "73") (name "unconnected-(U17-RESV-Pad7)") (class "Default")
      (node (ref "U17") (pin "7") (pinfunction "RESV_7") (pintype "unspecified+no_connect"))
    )
    (net (code "74") (name "unconnected-(USB1-ID-Pad4)") (class "Default")
      (node (ref "USB1") (pin "4") (pinfunction "ID_4") (pintype "unspecified+no_connect"))
    )
    (net (code "75") (name "unconnected-(X3-GND-Pad2)") (class "Default")
      (node (ref "X3") (pin "2") (pinfunction "GND_2") (pintype "unspecified+no_connect"))
    )
    (net (code "76") (name "unconnected-(X3-GND-Pad4)") (class "Default")
      (node (ref "X3") (pin "4") (pinfunction "GND_4") (pintype "unspecified+no_connect"))
    )
  )
)
